# M7103.net
KiCad netlist of a schematic drawn in EAGLE
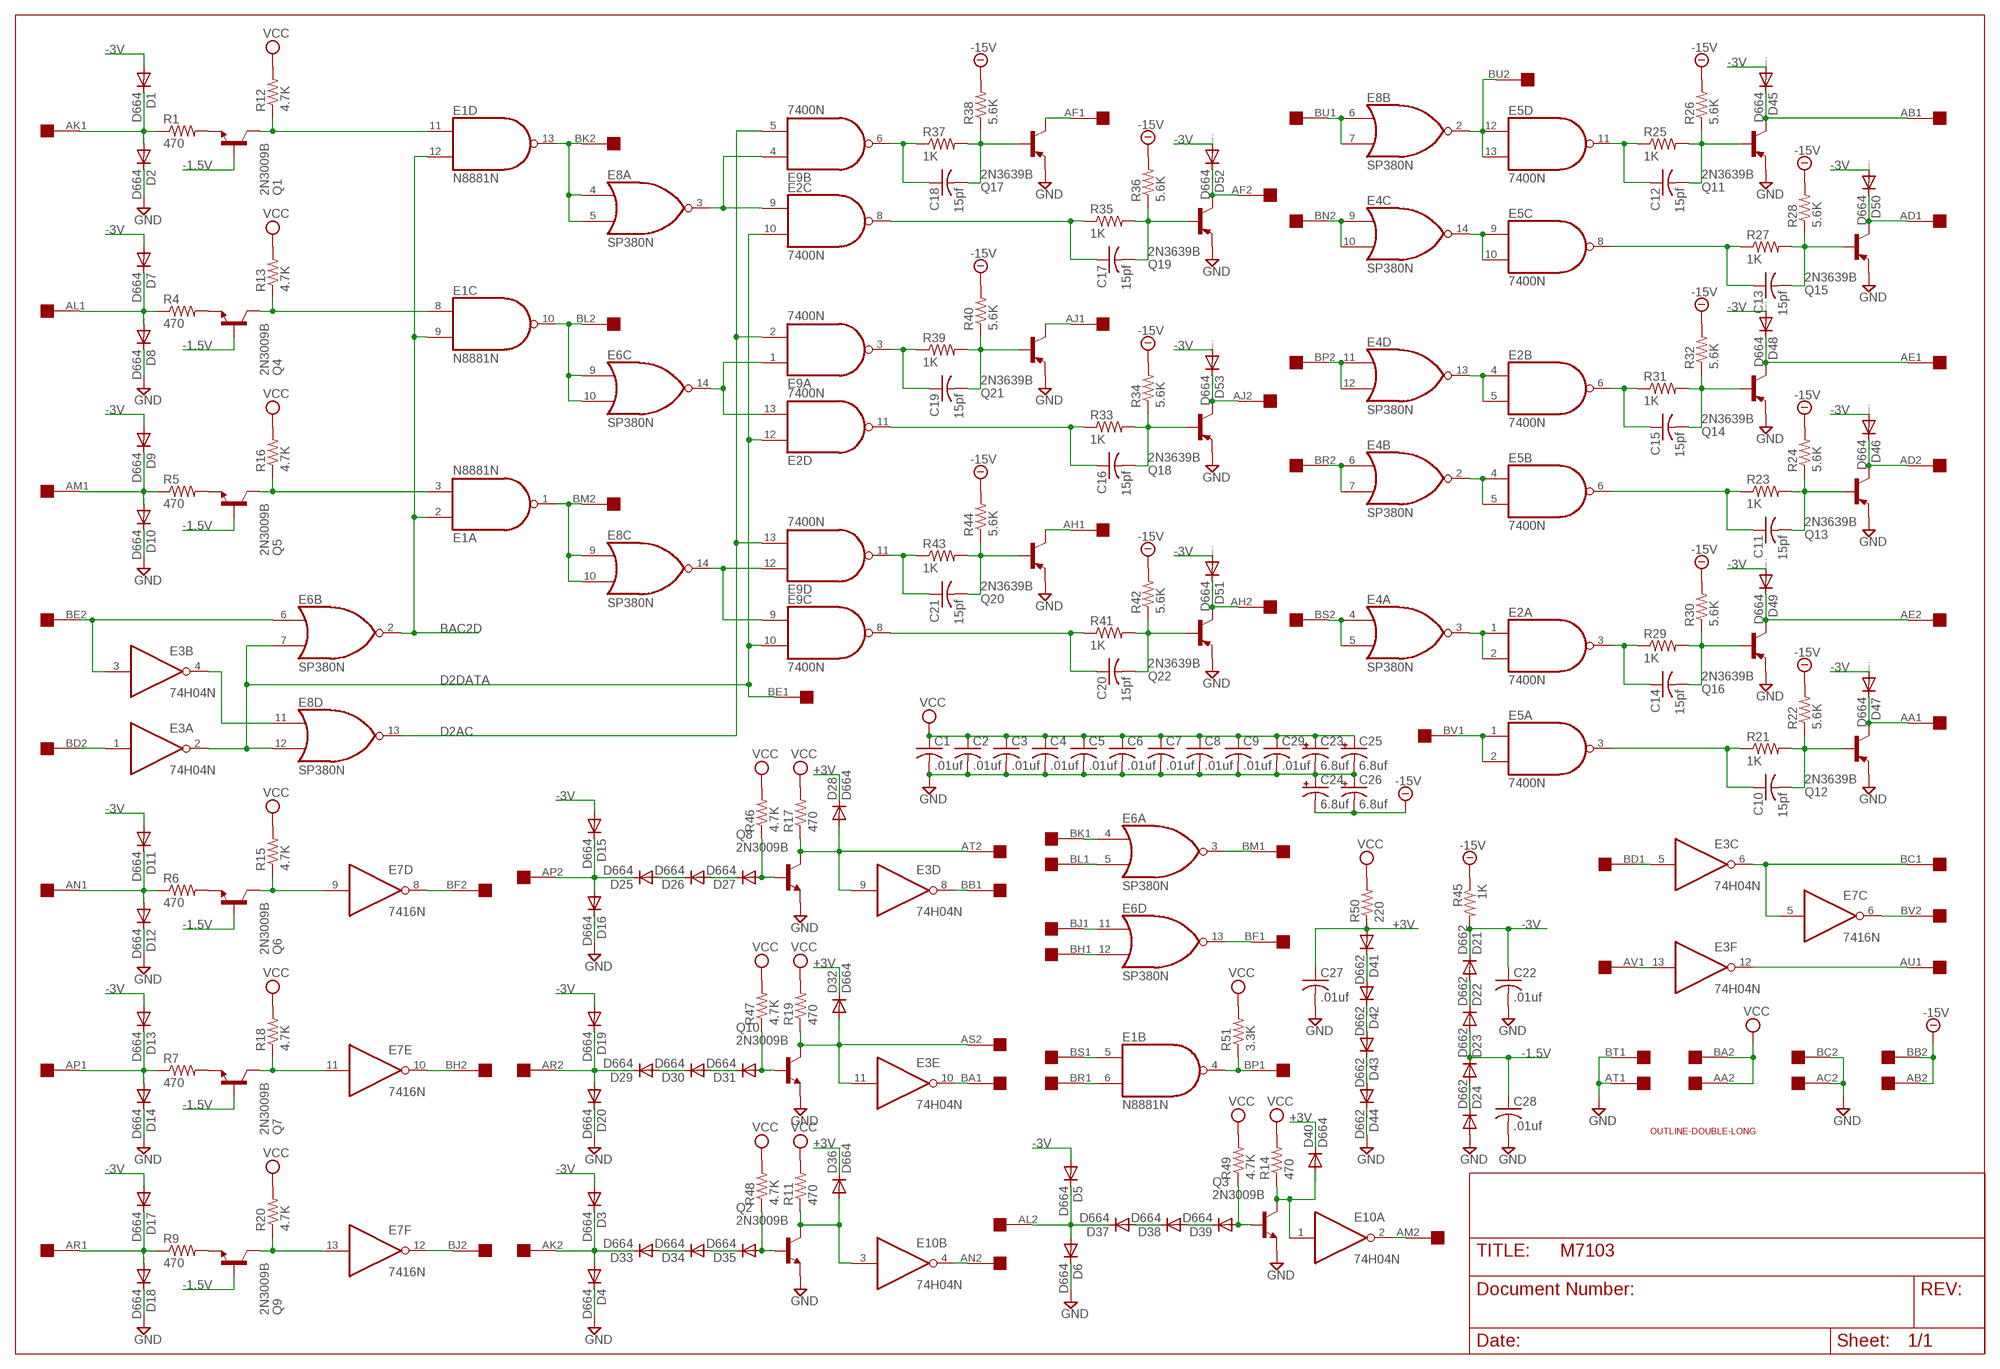
[diagram p0: schematic, sheet 1]

(export (version "E")
  (design (tool "Eeschema 10.0.6"))
  (components
    (comp (ref "C1")
      (value ".01uf")
      (footprint "eagle-import:C050-025X075")
      (libsource (lib "eagle-import") (part "C-US050-025X075"))
    )
    (comp (ref "C2")
      (value ".01uf")
      (footprint "eagle-import:C050-025X075")
      (libsource (lib "eagle-import") (part "C-US050-025X075"))
    )
    (comp (ref "C3")
      (value ".01uf")
      (footprint "eagle-import:C050-025X075")
      (libsource (lib "eagle-import") (part "C-US050-025X075"))
    )
    (comp (ref "C4")
      (value ".01uf")
      (footprint "eagle-import:C050-025X075")
      (libsource (lib "eagle-import") (part "C-US050-025X075"))
    )
    (comp (ref "C5")
      (value ".01uf")
      (footprint "eagle-import:C050-025X075")
      (libsource (lib "eagle-import") (part "C-US050-025X075"))
    )
    (comp (ref "C6")
      (value ".01uf")
      (footprint "eagle-import:C050-025X075")
      (libsource (lib "eagle-import") (part "C-US050-025X075"))
    )
    (comp (ref "C7")
      (value ".01uf")
      (footprint "eagle-import:C050-025X075")
      (libsource (lib "eagle-import") (part "C-US050-025X075"))
    )
    (comp (ref "C8")
      (value ".01uf")
      (footprint "eagle-import:C050-025X075")
      (libsource (lib "eagle-import") (part "C-US050-025X075"))
    )
    (comp (ref "C9")
      (value ".01uf")
      (footprint "eagle-import:C050-025X075")
      (libsource (lib "eagle-import") (part "C-US050-025X075"))
    )
    (comp (ref "C10")
      (value "15pf")
      (footprint "eagle-import:C050-025X075")
      (libsource (lib "eagle-import") (part "C-US050-025X075"))
    )
    (comp (ref "C11")
      (value "15pf")
      (footprint "eagle-import:C050-025X075")
      (libsource (lib "eagle-import") (part "C-US050-025X075"))
    )
    (comp (ref "C12")
      (value "15pf")
      (footprint "eagle-import:C050-025X075")
      (libsource (lib "eagle-import") (part "C-US050-025X075"))
    )
    (comp (ref "C13")
      (value "15pf")
      (footprint "eagle-import:C050-025X075")
      (libsource (lib "eagle-import") (part "C-US050-025X075"))
    )
    (comp (ref "C14")
      (value "15pf")
      (footprint "eagle-import:C050-025X075")
      (libsource (lib "eagle-import") (part "C-US050-025X075"))
    )
    (comp (ref "C15")
      (value "15pf")
      (footprint "eagle-import:C050-025X075")
      (libsource (lib "eagle-import") (part "C-US050-025X075"))
    )
    (comp (ref "C16")
      (value "15pf")
      (footprint "eagle-import:C050-025X075")
      (libsource (lib "eagle-import") (part "C-US050-025X075"))
    )
    (comp (ref "C17")
      (value "15pf")
      (footprint "eagle-import:C050-025X075")
      (libsource (lib "eagle-import") (part "C-US050-025X075"))
    )
    (comp (ref "C18")
      (value "15pf")
      (footprint "eagle-import:C050-025X075")
      (libsource (lib "eagle-import") (part "C-US050-025X075"))
    )
    (comp (ref "C19")
      (value "15pf")
      (footprint "eagle-import:C050-025X075")
      (libsource (lib "eagle-import") (part "C-US050-025X075"))
    )
    (comp (ref "C20")
      (value "15pf")
      (footprint "eagle-import:C050-025X075")
      (libsource (lib "eagle-import") (part "C-US050-025X075"))
    )
    (comp (ref "C21")
      (value "15pf")
      (footprint "eagle-import:C050-025X075")
      (libsource (lib "eagle-import") (part "C-US050-025X075"))
    )
    (comp (ref "C22")
      (value ".01uf")
      (footprint "eagle-import:C050-025X075")
      (libsource (lib "eagle-import") (part "C-US050-025X075"))
    )
    (comp (ref "C23")
      (value "6.8uf")
      (footprint "eagle-import:E15-5")
      (libsource (lib "eagle-import") (part "CPOL-USE15-5AXIAL"))
    )
    (comp (ref "C24")
      (value "6.8uf")
      (footprint "eagle-import:E15-5")
      (libsource (lib "eagle-import") (part "CPOL-USE15-5AXIAL"))
    )
    (comp (ref "C25")
      (value "6.8uf")
      (footprint "eagle-import:E15-5")
      (libsource (lib "eagle-import") (part "CPOL-USE15-5AXIAL"))
    )
    (comp (ref "C26")
      (value "6.8uf")
      (footprint "eagle-import:E15-5")
      (libsource (lib "eagle-import") (part "CPOL-USE15-5AXIAL"))
    )
    (comp (ref "C27")
      (value ".01uf")
      (footprint "eagle-import:C050-025X075")
      (libsource (lib "eagle-import") (part "C-US050-025X075"))
    )
    (comp (ref "C28")
      (value ".01uf")
      (footprint "eagle-import:C050-025X075")
      (libsource (lib "eagle-import") (part "C-US050-025X075"))
    )
    (comp (ref "C29")
      (value ".01uf")
      (footprint "eagle-import:C050-025X075")
      (libsource (lib "eagle-import") (part "C-US050-025X075"))
    )
    (comp (ref "D1")
      (value "D664")
      (footprint "eagle-import:DO35-10")
      (libsource (lib "eagle-import") (part "1N4148DO35-10"))
    )
    (comp (ref "D2")
      (value "D664")
      (footprint "eagle-import:DO35-10")
      (libsource (lib "eagle-import") (part "1N4148DO35-10"))
    )
    (comp (ref "D3")
      (value "D664")
      (footprint "eagle-import:DO35-10")
      (libsource (lib "eagle-import") (part "1N4148DO35-10"))
    )
    (comp (ref "D4")
      (value "D664")
      (footprint "eagle-import:DO35-10")
      (libsource (lib "eagle-import") (part "1N4148DO35-10"))
    )
    (comp (ref "D5")
      (value "D664")
      (footprint "eagle-import:DO35-10")
      (libsource (lib "eagle-import") (part "1N4148DO35-10"))
    )
    (comp (ref "D6")
      (value "D664")
      (footprint "eagle-import:DO35-10")
      (libsource (lib "eagle-import") (part "1N4148DO35-10"))
    )
    (comp (ref "D7")
      (value "D664")
      (footprint "eagle-import:DO35-10")
      (libsource (lib "eagle-import") (part "1N4148DO35-10"))
    )
    (comp (ref "D8")
      (value "D664")
      (footprint "eagle-import:DO35-10")
      (libsource (lib "eagle-import") (part "1N4148DO35-10"))
    )
    (comp (ref "D9")
      (value "D664")
      (footprint "eagle-import:DO35-10")
      (libsource (lib "eagle-import") (part "1N4148DO35-10"))
    )
    (comp (ref "D10")
      (value "D664")
      (footprint "eagle-import:DO35-10")
      (libsource (lib "eagle-import") (part "1N4148DO35-10"))
    )
    (comp (ref "D11")
      (value "D664")
      (footprint "eagle-import:DO35-10")
      (libsource (lib "eagle-import") (part "1N4148DO35-10"))
    )
    (comp (ref "D12")
      (value "D664")
      (footprint "eagle-import:DO35-10")
      (libsource (lib "eagle-import") (part "1N4148DO35-10"))
    )
    (comp (ref "D13")
      (value "D664")
      (footprint "eagle-import:DO35-10")
      (libsource (lib "eagle-import") (part "1N4148DO35-10"))
    )
    (comp (ref "D14")
      (value "D664")
      (footprint "eagle-import:DO35-10")
      (libsource (lib "eagle-import") (part "1N4148DO35-10"))
    )
    (comp (ref "D15")
      (value "D664")
      (footprint "eagle-import:DO35-10")
      (libsource (lib "eagle-import") (part "1N4148DO35-10"))
    )
    (comp (ref "D16")
      (value "D664")
      (footprint "eagle-import:DO35-10")
      (libsource (lib "eagle-import") (part "1N4148DO35-10"))
    )
    (comp (ref "D17")
      (value "D664")
      (footprint "eagle-import:DO35-10")
      (libsource (lib "eagle-import") (part "1N4148DO35-10"))
    )
    (comp (ref "D18")
      (value "D664")
      (footprint "eagle-import:DO35-10")
      (libsource (lib "eagle-import") (part "1N4148DO35-10"))
    )
    (comp (ref "D19")
      (value "D664")
      (footprint "eagle-import:DO35-10")
      (libsource (lib "eagle-import") (part "1N4148DO35-10"))
    )
    (comp (ref "D20")
      (value "D664")
      (footprint "eagle-import:DO35-10")
      (libsource (lib "eagle-import") (part "1N4148DO35-10"))
    )
    (comp (ref "D21")
      (value "D662")
      (footprint "eagle-import:DO35-10")
      (libsource (lib "eagle-import") (part "1N4148DO35-10"))
    )
    (comp (ref "D22")
      (value "D662")
      (footprint "eagle-import:DO35-10")
      (libsource (lib "eagle-import") (part "1N4148DO35-10"))
    )
    (comp (ref "D23")
      (value "D662")
      (footprint "eagle-import:DO35-10")
      (libsource (lib "eagle-import") (part "1N4148DO35-10"))
    )
    (comp (ref "D24")
      (value "D662")
      (footprint "eagle-import:DO35-10")
      (libsource (lib "eagle-import") (part "1N4148DO35-10"))
    )
    (comp (ref "D25")
      (value "D664")
      (footprint "eagle-import:DO35-10")
      (libsource (lib "eagle-import") (part "1N4148DO35-10"))
    )
    (comp (ref "D26")
      (value "D664")
      (footprint "eagle-import:DO35-10")
      (libsource (lib "eagle-import") (part "1N4148DO35-10"))
    )
    (comp (ref "D27")
      (value "D664")
      (footprint "eagle-import:DO35-10")
      (libsource (lib "eagle-import") (part "1N4148DO35-10"))
    )
    (comp (ref "D28")
      (value "D664")
      (footprint "eagle-import:DO35-10")
      (libsource (lib "eagle-import") (part "1N4148DO35-10"))
    )
    (comp (ref "D29")
      (value "D664")
      (footprint "eagle-import:DO35-10")
      (libsource (lib "eagle-import") (part "1N4148DO35-10"))
    )
    (comp (ref "D30")
      (value "D664")
      (footprint "eagle-import:DO35-10")
      (libsource (lib "eagle-import") (part "1N4148DO35-10"))
    )
    (comp (ref "D31")
      (value "D664")
      (footprint "eagle-import:DO35-10")
      (libsource (lib "eagle-import") (part "1N4148DO35-10"))
    )
    (comp (ref "D32")
      (value "D664")
      (footprint "eagle-import:DO35-10")
      (libsource (lib "eagle-import") (part "1N4148DO35-10"))
    )
    (comp (ref "D33")
      (value "D664")
      (footprint "eagle-import:DO35-10")
      (libsource (lib "eagle-import") (part "1N4148DO35-10"))
    )
    (comp (ref "D34")
      (value "D664")
      (footprint "eagle-import:DO35-10")
      (libsource (lib "eagle-import") (part "1N4148DO35-10"))
    )
    (comp (ref "D35")
      (value "D664")
      (footprint "eagle-import:DO35-10")
      (libsource (lib "eagle-import") (part "1N4148DO35-10"))
    )
    (comp (ref "D36")
      (value "D664")
      (footprint "eagle-import:DO35-10")
      (libsource (lib "eagle-import") (part "1N4148DO35-10"))
    )
    (comp (ref "D37")
      (value "D664")
      (footprint "eagle-import:DO35-10")
      (libsource (lib "eagle-import") (part "1N4148DO35-10"))
    )
    (comp (ref "D38")
      (value "D664")
      (footprint "eagle-import:DO35-10")
      (libsource (lib "eagle-import") (part "1N4148DO35-10"))
    )
    (comp (ref "D39")
      (value "D664")
      (footprint "eagle-import:DO35-10")
      (libsource (lib "eagle-import") (part "1N4148DO35-10"))
    )
    (comp (ref "D40")
      (value "D664")
      (footprint "eagle-import:DO35-10")
      (libsource (lib "eagle-import") (part "1N4148DO35-10"))
    )
    (comp (ref "D41")
      (value "D662")
      (footprint "eagle-import:DO35-10")
      (libsource (lib "eagle-import") (part "1N4148DO35-10"))
    )
    (comp (ref "D42")
      (value "D662")
      (footprint "eagle-import:DO35-10")
      (libsource (lib "eagle-import") (part "1N4148DO35-10"))
    )
    (comp (ref "D43")
      (value "D662")
      (footprint "eagle-import:DO35-10")
      (libsource (lib "eagle-import") (part "1N4148DO35-10"))
    )
    (comp (ref "D44")
      (value "D662")
      (footprint "eagle-import:DO35-10")
      (libsource (lib "eagle-import") (part "1N4148DO35-10"))
    )
    (comp (ref "D45")
      (value "D664")
      (footprint "eagle-import:DO35-10")
      (libsource (lib "eagle-import") (part "1N4148DO35-10"))
    )
    (comp (ref "D46")
      (value "D664")
      (footprint "eagle-import:DO35-10")
      (libsource (lib "eagle-import") (part "1N4148DO35-10"))
    )
    (comp (ref "D47")
      (value "D664")
      (footprint "eagle-import:DO35-10")
      (libsource (lib "eagle-import") (part "1N4148DO35-10"))
    )
    (comp (ref "D48")
      (value "D664")
      (footprint "eagle-import:DO35-10")
      (libsource (lib "eagle-import") (part "1N4148DO35-10"))
    )
    (comp (ref "D49")
      (value "D664")
      (footprint "eagle-import:DO35-10")
      (libsource (lib "eagle-import") (part "1N4148DO35-10"))
    )
    (comp (ref "D50")
      (value "D664")
      (footprint "eagle-import:DO35-10")
      (libsource (lib "eagle-import") (part "1N4148DO35-10"))
    )
    (comp (ref "D51")
      (value "D664")
      (footprint "eagle-import:DO35-10")
      (libsource (lib "eagle-import") (part "1N4148DO35-10"))
    )
    (comp (ref "D52")
      (value "D664")
      (footprint "eagle-import:DO35-10")
      (libsource (lib "eagle-import") (part "1N4148DO35-10"))
    )
    (comp (ref "D53")
      (value "D664")
      (footprint "eagle-import:DO35-10")
      (libsource (lib "eagle-import") (part "1N4148DO35-10"))
    )
    (comp (ref "E1")
      (value "N8881N")
      (footprint "eagle-import:DIL14")
      (libsource (lib "eagle-import") (part "N8881N"))
    )
    (comp (ref "E2")
      (value "7400N")
      (footprint "eagle-import:DIL14")
      (libsource (lib "eagle-import") (part "7400N"))
    )
    (comp (ref "E3")
      (value "74H04N")
      (footprint "eagle-import:DIL14")
      (libsource (lib "eagle-import") (part "7404N"))
    )
    (comp (ref "E4")
      (value "SP380N")
      (footprint "eagle-import:DIL14")
      (libsource (lib "eagle-import") (part "SP380N"))
    )
    (comp (ref "E5")
      (value "7400N")
      (footprint "eagle-import:DIL14")
      (libsource (lib "eagle-import") (part "7400N"))
    )
    (comp (ref "E6")
      (value "SP380N")
      (footprint "eagle-import:DIL14")
      (libsource (lib "eagle-import") (part "SP380N"))
    )
    (comp (ref "E7")
      (value "7416N")
      (footprint "eagle-import:DIL14")
      (libsource (lib "eagle-import") (part "7416N"))
    )
    (comp (ref "E8")
      (value "SP380N")
      (footprint "eagle-import:DIL14")
      (libsource (lib "eagle-import") (part "SP380N"))
    )
    (comp (ref "E9")
      (value "7400N")
      (footprint "eagle-import:DIL14")
      (libsource (lib "eagle-import") (part "7400N"))
    )
    (comp (ref "E10")
      (value "74H04N")
      (footprint "eagle-import:DIL14")
      (libsource (lib "eagle-import") (part "7404N"))
    )
    (comp (ref "EDGE")
      (value "DOUBLE")
      (footprint "eagle-import:EDGE-CON4")
      (libsource (lib "eagle-import") (part "DOUBLE"))
    )
    (comp (ref "Q1")
      (value "2N3009B")
      (footprint "eagle-import:TO39")
      (libsource (lib "eagle-import") (part "2N3019"))
    )
    (comp (ref "Q2")
      (value "2N3009B")
      (footprint "eagle-import:TO39")
      (libsource (lib "eagle-import") (part "2N3019"))
    )
    (comp (ref "Q3")
      (value "2N3009B")
      (footprint "eagle-import:TO39")
      (libsource (lib "eagle-import") (part "2N3019"))
    )
    (comp (ref "Q4")
      (value "2N3009B")
      (footprint "eagle-import:TO39")
      (libsource (lib "eagle-import") (part "2N3019"))
    )
    (comp (ref "Q5")
      (value "2N3009B")
      (footprint "eagle-import:TO39")
      (libsource (lib "eagle-import") (part "2N3019"))
    )
    (comp (ref "Q6")
      (value "2N3009B")
      (footprint "eagle-import:TO39")
      (libsource (lib "eagle-import") (part "2N3019"))
    )
    (comp (ref "Q7")
      (value "2N3009B")
      (footprint "eagle-import:TO39")
      (libsource (lib "eagle-import") (part "2N3019"))
    )
    (comp (ref "Q8")
      (value "2N3009B")
      (footprint "eagle-import:TO39")
      (libsource (lib "eagle-import") (part "2N3019"))
    )
    (comp (ref "Q9")
      (value "2N3009B")
      (footprint "eagle-import:TO39")
      (libsource (lib "eagle-import") (part "2N3019"))
    )
    (comp (ref "Q10")
      (value "2N3009B")
      (footprint "eagle-import:TO39")
      (libsource (lib "eagle-import") (part "2N3019"))
    )
    (comp (ref "Q11")
      (value "2N3639B")
      (footprint "eagle-import:TO39")
      (libsource (lib "eagle-import") (part "2N3637"))
    )
    (comp (ref "Q12")
      (value "2N3639B")
      (footprint "eagle-import:TO39")
      (libsource (lib "eagle-import") (part "2N3637"))
    )
    (comp (ref "Q13")
      (value "2N3639B")
      (footprint "eagle-import:TO39")
      (libsource (lib "eagle-import") (part "2N3637"))
    )
    (comp (ref "Q14")
      (value "2N3639B")
      (footprint "eagle-import:TO39")
      (libsource (lib "eagle-import") (part "2N3637"))
    )
    (comp (ref "Q15")
      (value "2N3639B")
      (footprint "eagle-import:TO39")
      (libsource (lib "eagle-import") (part "2N3637"))
    )
    (comp (ref "Q16")
      (value "2N3639B")
      (footprint "eagle-import:TO39")
      (libsource (lib "eagle-import") (part "2N3637"))
    )
    (comp (ref "Q17")
      (value "2N3639B")
      (footprint "eagle-import:TO39")
      (libsource (lib "eagle-import") (part "2N3637"))
    )
    (comp (ref "Q18")
      (value "2N3639B")
      (footprint "eagle-import:TO39")
      (libsource (lib "eagle-import") (part "2N3637"))
    )
    (comp (ref "Q19")
      (value "2N3639B")
      (footprint "eagle-import:TO39")
      (libsource (lib "eagle-import") (part "2N3637"))
    )
    (comp (ref "Q20")
      (value "2N3639B")
      (footprint "eagle-import:TO39")
      (libsource (lib "eagle-import") (part "2N3637"))
    )
    (comp (ref "Q21")
      (value "2N3639B")
      (footprint "eagle-import:TO39")
      (libsource (lib "eagle-import") (part "2N3637"))
    )
    (comp (ref "Q22")
      (value "2N3639B")
      (footprint "eagle-import:TO39")
      (libsource (lib "eagle-import") (part "2N3637"))
    )
    (comp (ref "R1")
      (value "470")
      (footprint "eagle-import:0207_10")
      (libsource (lib "eagle-import") (part "R-US_0207/10"))
    )
    (comp (ref "R4")
      (value "470")
      (footprint "eagle-import:0207_10")
      (libsource (lib "eagle-import") (part "R-US_0207/10"))
    )
    (comp (ref "R5")
      (value "470")
      (footprint "eagle-import:0207_10")
      (libsource (lib "eagle-import") (part "R-US_0207/10"))
    )
    (comp (ref "R6")
      (value "470")
      (footprint "eagle-import:0207_10")
      (libsource (lib "eagle-import") (part "R-US_0207/10"))
    )
    (comp (ref "R7")
      (value "470")
      (footprint "eagle-import:0207_10")
      (libsource (lib "eagle-import") (part "R-US_0207/10"))
    )
    (comp (ref "R9")
      (value "470")
      (footprint "eagle-import:0207_10")
      (libsource (lib "eagle-import") (part "R-US_0207/10"))
    )
    (comp (ref "R11")
      (value "470")
      (footprint "eagle-import:0207_10")
      (libsource (lib "eagle-import") (part "R-US_0207/10"))
    )
    (comp (ref "R12")
      (value "4.7K")
      (footprint "eagle-import:0207_10")
      (libsource (lib "eagle-import") (part "R-US_0207/10"))
    )
    (comp (ref "R13")
      (value "4.7K")
      (footprint "eagle-import:0207_10")
      (libsource (lib "eagle-import") (part "R-US_0207/10"))
    )
    (comp (ref "R14")
      (value "470")
      (footprint "eagle-import:0207_10")
      (libsource (lib "eagle-import") (part "R-US_0207/10"))
    )
    (comp (ref "R15")
      (value "4.7K")
      (footprint "eagle-import:0207_10")
      (libsource (lib "eagle-import") (part "R-US_0207/10"))
    )
    (comp (ref "R16")
      (value "4.7K")
      (footprint "eagle-import:0207_10")
      (libsource (lib "eagle-import") (part "R-US_0207/10"))
    )
    (comp (ref "R17")
      (value "470")
      (footprint "eagle-import:0207_10")
      (libsource (lib "eagle-import") (part "R-US_0207/10"))
    )
    (comp (ref "R18")
      (value "4.7K")
      (footprint "eagle-import:0207_10")
      (libsource (lib "eagle-import") (part "R-US_0207/10"))
    )
    (comp (ref "R19")
      (value "470")
      (footprint "eagle-import:0207_10")
      (libsource (lib "eagle-import") (part "R-US_0207/10"))
    )
    (comp (ref "R20")
      (value "4.7K")
      (footprint "eagle-import:0207_10")
      (libsource (lib "eagle-import") (part "R-US_0207/10"))
    )
    (comp (ref "R21")
      (value "1K")
      (footprint "eagle-import:0207_10")
      (libsource (lib "eagle-import") (part "R-US_0207/10"))
    )
    (comp (ref "R22")
      (value "5.6K")
      (footprint "eagle-import:0207_10")
      (libsource (lib "eagle-import") (part "R-US_0207/10"))
    )
    (comp (ref "R23")
      (value "1K")
      (footprint "eagle-import:0207_10")
      (libsource (lib "eagle-import") (part "R-US_0207/10"))
    )
    (comp (ref "R24")
      (value "5.6K")
      (footprint "eagle-import:0207_10")
      (libsource (lib "eagle-import") (part "R-US_0207/10"))
    )
    (comp (ref "R25")
      (value "1K")
      (footprint "eagle-import:0207_10")
      (libsource (lib "eagle-import") (part "R-US_0207/10"))
    )
    (comp (ref "R26")
      (value "5.6K")
      (footprint "eagle-import:0207_10")
      (libsource (lib "eagle-import") (part "R-US_0207/10"))
    )
    (comp (ref "R27")
      (value "1K")
      (footprint "eagle-import:0207_10")
      (libsource (lib "eagle-import") (part "R-US_0207/10"))
    )
    (comp (ref "R28")
      (value "5.6K")
      (footprint "eagle-import:0207_10")
      (libsource (lib "eagle-import") (part "R-US_0207/10"))
    )
    (comp (ref "R29")
      (value "1K")
      (footprint "eagle-import:0207_10")
      (libsource (lib "eagle-import") (part "R-US_0207/10"))
    )
    (comp (ref "R30")
      (value "5.6K")
      (footprint "eagle-import:0207_10")
      (libsource (lib "eagle-import") (part "R-US_0207/10"))
    )
    (comp (ref "R31")
      (value "1K")
      (footprint "eagle-import:0207_10")
      (libsource (lib "eagle-import") (part "R-US_0207/10"))
    )
    (comp (ref "R32")
      (value "5.6K")
      (footprint "eagle-import:0207_10")
      (libsource (lib "eagle-import") (part "R-US_0207/10"))
    )
    (comp (ref "R33")
      (value "1K")
      (footprint "eagle-import:0207_10")
      (libsource (lib "eagle-import") (part "R-US_0207/10"))
    )
    (comp (ref "R34")
      (value "5.6K")
      (footprint "eagle-import:0207_10")
      (libsource (lib "eagle-import") (part "R-US_0207/10"))
    )
    (comp (ref "R35")
      (value "1K")
      (footprint "eagle-import:0207_10")
      (libsource (lib "eagle-import") (part "R-US_0207/10"))
    )
    (comp (ref "R36")
      (value "5.6K")
      (footprint "eagle-import:0207_10")
      (libsource (lib "eagle-import") (part "R-US_0207/10"))
    )
    (comp (ref "R37")
      (value "1K")
      (footprint "eagle-import:0207_10")
      (libsource (lib "eagle-import") (part "R-US_0207/10"))
    )
    (comp (ref "R38")
      (value "5.6K")
      (footprint "eagle-import:0207_10")
      (libsource (lib "eagle-import") (part "R-US_0207/10"))
    )
    (comp (ref "R39")
      (value "1K")
      (footprint "eagle-import:0207_10")
      (libsource (lib "eagle-import") (part "R-US_0207/10"))
    )
    (comp (ref "R40")
      (value "5.6K")
      (footprint "eagle-import:0207_10")
      (libsource (lib "eagle-import") (part "R-US_0207/10"))
    )
    (comp (ref "R41")
      (value "1K")
      (footprint "eagle-import:0207_10")
      (libsource (lib "eagle-import") (part "R-US_0207/10"))
    )
    (comp (ref "R42")
      (value "5.6K")
      (footprint "eagle-import:0207_10")
      (libsource (lib "eagle-import") (part "R-US_0207/10"))
    )
    (comp (ref "R43")
      (value "1K")
      (footprint "eagle-import:0207_10")
      (libsource (lib "eagle-import") (part "R-US_0207/10"))
    )
    (comp (ref "R44")
      (value "5.6K")
      (footprint "eagle-import:0207_10")
      (libsource (lib "eagle-import") (part "R-US_0207/10"))
    )
    (comp (ref "R45")
      (value "1K")
      (footprint "eagle-import:0207_10")
      (libsource (lib "eagle-import") (part "R-US_0207/10"))
    )
    (comp (ref "R46")
      (value "4.7K")
      (footprint "eagle-import:0207_10")
      (libsource (lib "eagle-import") (part "R-US_0207/10"))
    )
    (comp (ref "R47")
      (value "4.7K")
      (footprint "eagle-import:0207_10")
      (libsource (lib "eagle-import") (part "R-US_0207/10"))
    )
    (comp (ref "R48")
      (value "4.7K")
      (footprint "eagle-import:0207_10")
      (libsource (lib "eagle-import") (part "R-US_0207/10"))
    )
    (comp (ref "R49")
      (value "4.7K")
      (footprint "eagle-import:0207_10")
      (libsource (lib "eagle-import") (part "R-US_0207/10"))
    )
    (comp (ref "R50")
      (value "220")
      (footprint "eagle-import:0207_10")
      (libsource (lib "eagle-import") (part "R-US_0207/10"))
    )
    (comp (ref "R51")
      (value "3.3K")
      (footprint "eagle-import:0207_10")
      (libsource (lib "eagle-import") (part "R-US_0207/10"))
    )
    (comp (ref "U$3")
      (value "OUTLINE-DOUBLE-LONG")
      (footprint "eagle-import:DOUBLE-LONG")
      (libsource (lib "eagle-import") (part "OUTLINE-DOUBLE-LONG"))
    )
  )
  (nets
    (net (code "1") (name "-15V") (class "Default")
      (node (ref "C24") (pin "-") (pinfunction "-_-") (pintype "passive"))
      (node (ref "C26") (pin "-") (pinfunction "-_-") (pintype "passive"))
      (node (ref "EDGE") (pin "AB2") (pinfunction "1_AB2") (pintype "bidirectional"))
      (node (ref "EDGE") (pin "BB2") (pinfunction "1_BB2") (pintype "bidirectional"))
      (node (ref "R22") (pin "2") (pinfunction "2_2") (pintype "passive"))
      (node (ref "R24") (pin "2") (pinfunction "2_2") (pintype "passive"))
      (node (ref "R26") (pin "2") (pinfunction "2_2") (pintype "passive"))
      (node (ref "R28") (pin "2") (pinfunction "2_2") (pintype "passive"))
      (node (ref "R30") (pin "2") (pinfunction "2_2") (pintype "passive"))
      (node (ref "R32") (pin "2") (pinfunction "2_2") (pintype "passive"))
      (node (ref "R34") (pin "2") (pinfunction "2_2") (pintype "passive"))
      (node (ref "R36") (pin "2") (pinfunction "2_2") (pintype "passive"))
      (node (ref "R38") (pin "2") (pinfunction "2_2") (pintype "passive"))
      (node (ref "R40") (pin "2") (pinfunction "2_2") (pintype "passive"))
      (node (ref "R42") (pin "2") (pinfunction "2_2") (pintype "passive"))
      (node (ref "R44") (pin "2") (pinfunction "2_2") (pintype "passive"))
      (node (ref "R45") (pin "1") (pinfunction "1_1") (pintype "passive"))
    )
    (net (code "2") (name "/+3V") (class "Default")
      (node (ref "C27") (pin "1") (pinfunction "1_1") (pintype "passive"))
      (node (ref "D28") (pin "C") (pinfunction "C_C") (pintype "passive"))
      (node (ref "D32") (pin "C") (pinfunction "C_C") (pintype "passive"))
      (node (ref "D36") (pin "C") (pinfunction "C_C") (pintype "passive"))
      (node (ref "D40") (pin "C") (pinfunction "C_C") (pintype "passive"))
      (node (ref "D41") (pin "A") (pinfunction "A_A") (pintype "passive"))
      (node (ref "R50") (pin "1") (pinfunction "1_1") (pintype "passive"))
    )
    (net (code "3") (name "/-1.5V") (class "Default")
      (node (ref "C28") (pin "1") (pinfunction "1_1") (pintype "passive"))
      (node (ref "D22") (pin "A") (pinfunction "A_A") (pintype "passive"))
      (node (ref "D23") (pin "C") (pinfunction "C_C") (pintype "passive"))
      (node (ref "Q1") (pin "2") (pinfunction "B_2") (pintype "passive"))
      (node (ref "Q4") (pin "2") (pinfunction "B_2") (pintype "passive"))
      (node (ref "Q5") (pin "2") (pinfunction "B_2") (pintype "passive"))
      (node (ref "Q6") (pin "2") (pinfunction "B_2") (pintype "passive"))
      (node (ref "Q7") (pin "2") (pinfunction "B_2") (pintype "passive"))
      (node (ref "Q9") (pin "2") (pinfunction "B_2") (pintype "passive"))
    )
    (net (code "4") (name "/-3V") (class "Default")
      (node (ref "C22") (pin "1") (pinfunction "1_1") (pintype "passive"))
      (node (ref "D1") (pin "A") (pinfunction "A_A") (pintype "passive"))
      (node (ref "D11") (pin "A") (pinfunction "A_A") (pintype "passive"))
      (node (ref "D13") (pin "A") (pinfunction "A_A") (pintype "passive"))
      (node (ref "D15") (pin "A") (pinfunction "A_A") (pintype "passive"))
      (node (ref "D17") (pin "A") (pinfunction "A_A") (pintype "passive"))
      (node (ref "D19") (pin "A") (pinfunction "A_A") (pintype "passive"))
      (node (ref "D21") (pin "C") (pinfunction "C_C") (pintype "passive"))
      (node (ref "D3") (pin "A") (pinfunction "A_A") (pintype "passive"))
      (node (ref "D45") (pin "A") (pinfunction "A_A") (pintype "passive"))
      (node (ref "D46") (pin "A") (pinfunction "A_A") (pintype "passive"))
      (node (ref "D47") (pin "A") (pinfunction "A_A") (pintype "passive"))
      (node (ref "D48") (pin "A") (pinfunction "A_A") (pintype "passive"))
      (node (ref "D49") (pin "A") (pinfunction "A_A") (pintype "passive"))
      (node (ref "D5") (pin "A") (pinfunction "A_A") (pintype "passive"))
      (node (ref "D50") (pin "A") (pinfunction "A_A") (pintype "passive"))
      (node (ref "D51") (pin "A") (pinfunction "A_A") (pintype "passive"))
      (node (ref "D52") (pin "A") (pinfunction "A_A") (pintype "passive"))
      (node (ref "D53") (pin "A") (pinfunction "A_A") (pintype "passive"))
      (node (ref "D7") (pin "A") (pinfunction "A_A") (pintype "passive"))
      (node (ref "D9") (pin "A") (pinfunction "A_A") (pintype "passive"))
      (node (ref "R45") (pin "2") (pinfunction "2_2") (pintype "passive"))
    )
    (net (code "5") (name "/BAC2D") (class "Default")
      (node (ref "E1") (pin "12") (pinfunction "I1_12") (pintype "input"))
      (node (ref "E1") (pin "2") (pinfunction "I0_2") (pintype "input"))
      (node (ref "E1") (pin "9") (pinfunction "I1_9") (pintype "input"))
      (node (ref "E6") (pin "2") (pinfunction "O_2") (pintype "output"))
    )
    (net (code "6") (name "/D2AC") (class "Default")
      (node (ref "E8") (pin "13") (pinfunction "O_13") (pintype "output"))
      (node (ref "E9") (pin "13") (pinfunction "I1_13") (pintype "input"))
      (node (ref "E9") (pin "2") (pinfunction "I1_2") (pintype "input"))
      (node (ref "E9") (pin "5") (pinfunction "I1_5") (pintype "input"))
    )
    (net (code "7") (name "/D2DATA") (class "Default")
      (node (ref "E2") (pin "10") (pinfunction "I1_10") (pintype "input"))
      (node (ref "E2") (pin "12") (pinfunction "I0_12") (pintype "input"))
      (node (ref "E3") (pin "2") (pinfunction "O_2") (pintype "output"))
      (node (ref "E6") (pin "7") (pinfunction "I1_7") (pintype "input"))
      (node (ref "E8") (pin "12") (pinfunction "I1_12") (pintype "input"))
      (node (ref "E9") (pin "10") (pinfunction "I1_10") (pintype "input"))
      (node (ref "EDGE") (pin "BE1") (pinfunction "1_BE1") (pintype "bidirectional"))
    )
    (net (code "8") (name "GND") (class "Default")
      (node (ref "C1") (pin "2") (pinfunction "2_2") (pintype "passive"))
      (node (ref "C2") (pin "2") (pinfunction "2_2") (pintype "passive"))
      (node (ref "C22") (pin "2") (pinfunction "2_2") (pintype "passive"))
      (node (ref "C23") (pin "-") (pinfunction "-_-") (pintype "passive"))
      (node (ref "C24") (pin "+") (pinfunction "+_+") (pintype "passive"))
      (node (ref "C25") (pin "-") (pinfunction "-_-") (pintype "passive"))
      (node (ref "C26") (pin "+") (pinfunction "+_+") (pintype "passive"))
      (node (ref "C27") (pin "2") (pinfunction "2_2") (pintype "passive"))
      (node (ref "C28") (pin "2") (pinfunction "2_2") (pintype "passive"))
      (node (ref "C29") (pin "2") (pinfunction "2_2") (pintype "passive"))
      (node (ref "C3") (pin "2") (pinfunction "2_2") (pintype "passive"))
      (node (ref "C4") (pin "2") (pinfunction "2_2") (pintype "passive"))
      (node (ref "C5") (pin "2") (pinfunction "2_2") (pintype "passive"))
      (node (ref "C6") (pin "2") (pinfunction "2_2") (pintype "passive"))
      (node (ref "C7") (pin "2") (pinfunction "2_2") (pintype "passive"))
      (node (ref "C8") (pin "2") (pinfunction "2_2") (pintype "passive"))
      (node (ref "C9") (pin "2") (pinfunction "2_2") (pintype "passive"))
      (node (ref "D10") (pin "C") (pinfunction "C_C") (pintype "passive"))
      (node (ref "D12") (pin "C") (pinfunction "C_C") (pintype "passive"))
      (node (ref "D14") (pin "C") (pinfunction "C_C") (pintype "passive"))
      (node (ref "D16") (pin "C") (pinfunction "C_C") (pintype "passive"))
      (node (ref "D18") (pin "C") (pinfunction "C_C") (pintype "passive"))
      (node (ref "D2") (pin "C") (pinfunction "C_C") (pintype "passive"))
      (node (ref "D20") (pin "C") (pinfunction "C_C") (pintype "passive"))
      (node (ref "D24") (pin "A") (pinfunction "A_A") (pintype "passive"))
      (node (ref "D4") (pin "C") (pinfunction "C_C") (pintype "passive"))
      (node (ref "D44") (pin "C") (pinfunction "C_C") (pintype "passive"))
      (node (ref "D6") (pin "C") (pinfunction "C_C") (pintype "passive"))
      (node (ref "D8") (pin "C") (pinfunction "C_C") (pintype "passive"))
      (node (ref "EDGE") (pin "AC2") (pinfunction "1_AC2") (pintype "bidirectional"))
      (node (ref "EDGE") (pin "AT1") (pinfunction "1_AT1") (pintype "bidirectional"))
      (node (ref "EDGE") (pin "BC2") (pinfunction "1_BC2") (pintype "bidirectional"))
      (node (ref "EDGE") (pin "BT1") (pinfunction "1_BT1") (pintype "bidirectional"))
      (node (ref "Q10") (pin "1") (pinfunction "E_1") (pintype "passive"))
      (node (ref "Q11") (pin "1") (pinfunction "E_1") (pintype "passive"))
      (node (ref "Q12") (pin "1") (pinfunction "E_1") (pintype "passive"))
      (node (ref "Q13") (pin "1") (pinfunction "E_1") (pintype "passive"))
      (node (ref "Q14") (pin "1") (pinfunction "E_1") (pintype "passive"))
      (node (ref "Q15") (pin "1") (pinfunction "E_1") (pintype "passive"))
      (node (ref "Q16") (pin "1") (pinfunction "E_1") (pintype "passive"))
      (node (ref "Q17") (pin "1") (pinfunction "E_1") (pintype "passive"))
      (node (ref "Q18") (pin "1") (pinfunction "E_1") (pintype "passive"))
      (node (ref "Q19") (pin "1") (pinfunction "E_1") (pintype "passive"))
      (node (ref "Q2") (pin "1") (pinfunction "E_1") (pintype "passive"))
      (node (ref "Q20") (pin "1") (pinfunction "E_1") (pintype "passive"))
      (node (ref "Q21") (pin "1") (pinfunction "E_1") (pintype "passive"))
      (node (ref "Q22") (pin "1") (pinfunction "E_1") (pintype "passive"))
      (node (ref "Q3") (pin "1") (pinfunction "E_1") (pintype "passive"))
      (node (ref "Q8") (pin "1") (pinfunction "E_1") (pintype "passive"))
    )
    (net (code "9") (name "Net-(D21-PadA)") (class "Default")
      (node (ref "D21") (pin "A") (pinfunction "A_A") (pintype "passive"))
      (node (ref "D22") (pin "C") (pinfunction "C_C") (pintype "passive"))
    )
    (net (code "10") (name "Net-(D23-PadA)") (class "Default")
      (node (ref "D23") (pin "A") (pinfunction "A_A") (pintype "passive"))
      (node (ref "D24") (pin "C") (pinfunction "C_C") (pintype "passive"))
    )
    (net (code "11") (name "Net-(D25-PadA)") (class "Default")
      (node (ref "D25") (pin "A") (pinfunction "A_A") (pintype "passive"))
      (node (ref "D26") (pin "C") (pinfunction "C_C") (pintype "passive"))
    )
    (net (code "12") (name "Net-(D26-PadA)") (class "Default")
      (node (ref "D26") (pin "A") (pinfunction "A_A") (pintype "passive"))
      (node (ref "D27") (pin "C") (pinfunction "C_C") (pintype "passive"))
    )
    (net (code "13") (name "Net-(D29-PadA)") (class "Default")
      (node (ref "D29") (pin "A") (pinfunction "A_A") (pintype "passive"))
      (node (ref "D30") (pin "C") (pinfunction "C_C") (pintype "passive"))
    )
    (net (code "14") (name "Net-(D30-PadA)") (class "Default")
      (node (ref "D30") (pin "A") (pinfunction "A_A") (pintype "passive"))
      (node (ref "D31") (pin "C") (pinfunction "C_C") (pintype "passive"))
    )
    (net (code "15") (name "Net-(D33-PadA)") (class "Default")
      (node (ref "D33") (pin "A") (pinfunction "A_A") (pintype "passive"))
      (node (ref "D34") (pin "C") (pinfunction "C_C") (pintype "passive"))
    )
    (net (code "16") (name "Net-(D34-PadA)") (class "Default")
      (node (ref "D34") (pin "A") (pinfunction "A_A") (pintype "passive"))
      (node (ref "D35") (pin "C") (pinfunction "C_C") (pintype "passive"))
    )
    (net (code "17") (name "Net-(D37-PadA)") (class "Default")
      (node (ref "D37") (pin "A") (pinfunction "A_A") (pintype "passive"))
      (node (ref "D38") (pin "C") (pinfunction "C_C") (pintype "passive"))
    )
    (net (code "18") (name "Net-(D38-PadA)") (class "Default")
      (node (ref "D38") (pin "A") (pinfunction "A_A") (pintype "passive"))
      (node (ref "D39") (pin "C") (pinfunction "C_C") (pintype "passive"))
    )
    (net (code "19") (name "Net-(D41-PadC)") (class "Default")
      (node (ref "D41") (pin "C") (pinfunction "C_C") (pintype "passive"))
      (node (ref "D42") (pin "A") (pinfunction "A_A") (pintype "passive"))
    )
    (net (code "20") (name "Net-(D42-PadC)") (class "Default")
      (node (ref "D42") (pin "C") (pinfunction "C_C") (pintype "passive"))
      (node (ref "D43") (pin "A") (pinfunction "A_A") (pintype "passive"))
    )
    (net (code "21") (name "Net-(D43-PadC)") (class "Default")
      (node (ref "D43") (pin "C") (pinfunction "C_C") (pintype "passive"))
      (node (ref "D44") (pin "A") (pinfunction "A_A") (pintype "passive"))
    )
    (net (code "22") (name "Net-(E1A-I1)") (class "Default")
      (node (ref "E1") (pin "3") (pinfunction "I1_3") (pintype "input"))
      (node (ref "Q5") (pin "3") (pinfunction "C_3") (pintype "passive"))
      (node (ref "R16") (pin "1") (pinfunction "1_1") (pintype "passive"))
    )
    (net (code "23") (name "Net-(E1A-O)") (class "Default")
      (node (ref "E1") (pin "1") (pinfunction "O_1") (pintype "open_collector"))
      (node (ref "E8") (pin "10") (pinfunction "I1_10") (pintype "input"))
      (node (ref "E8") (pin "9") (pinfunction "I0_9") (pintype "input"))
      (node (ref "EDGE") (pin "BM2") (pinfunction "1_BM2") (pintype "bidirectional"))
    )
    (net (code "24") (name "Net-(E1B-I0)") (class "Default")
      (node (ref "E1") (pin "5") (pinfunction "I0_5") (pintype "input"))
      (node (ref "EDGE") (pin "BS1") (pinfunction "1_BS1") (pintype "bidirectional"))
    )
    (net (code "25") (name "Net-(E1B-I1)") (class "Default")
      (node (ref "E1") (pin "6") (pinfunction "I1_6") (pintype "input"))
      (node (ref "EDGE") (pin "BR1") (pinfunction "1_BR1") (pintype "bidirectional"))
    )
    (net (code "26") (name "Net-(E1B-O)") (class "Default")
      (node (ref "E1") (pin "4") (pinfunction "O_4") (pintype "open_collector"))
      (node (ref "EDGE") (pin "BP1") (pinfunction "1_BP1") (pintype "bidirectional"))
      (node (ref "R51") (pin "1") (pinfunction "1_1") (pintype "passive"))
    )
    (net (code "27") (name "Net-(E1C-I0)") (class "Default")
      (node (ref "E1") (pin "8") (pinfunction "I0_8") (pintype "input"))
      (node (ref "Q4") (pin "3") (pinfunction "C_3") (pintype "passive"))
      (node (ref "R13") (pin "1") (pinfunction "1_1") (pintype "passive"))
    )
    (net (code "28") (name "Net-(E1C-O)") (class "Default")
      (node (ref "E1") (pin "10") (pinfunction "O_10") (pintype "open_collector"))
      (node (ref "E6") (pin "10") (pinfunction "I1_10") (pintype "input"))
      (node (ref "E6") (pin "9") (pinfunction "I0_9") (pintype "input"))
      (node (ref "EDGE") (pin "BL2") (pinfunction "1_BL2") (pintype "bidirectional"))
    )
    (net (code "29") (name "Net-(E1D-I0)") (class "Default")
      (node (ref "E1") (pin "11") (pinfunction "I0_11") (pintype "input"))
      (node (ref "Q1") (pin "3") (pinfunction "C_3") (pintype "passive"))
      (node (ref "R12") (pin "1") (pinfunction "1_1") (pintype "passive"))
    )
    (net (code "30") (name "Net-(E1D-O)") (class "Default")
      (node (ref "E1") (pin "13") (pinfunction "O_13") (pintype "open_collector"))
      (node (ref "E8") (pin "4") (pinfunction "I0_4") (pintype "input"))
      (node (ref "E8") (pin "5") (pinfunction "I1_5") (pintype "input"))
      (node (ref "EDGE") (pin "BK2") (pinfunction "1_BK2") (pintype "bidirectional"))
    )
    (net (code "31") (name "Net-(E2A-I0)") (class "Default")
      (node (ref "E2") (pin "1") (pinfunction "I0_1") (pintype "input"))
      (node (ref "E2") (pin "2") (pinfunction "I1_2") (pintype "input"))
      (node (ref "E4") (pin "3") (pinfunction "O_3") (pintype "output"))
    )
    (net (code "32") (name "Net-(E2A-O)") (class "Default")
      (node (ref "C14") (pin "1") (pinfunction "1_1") (pintype "passive"))
      (node (ref "E2") (pin "3") (pinfunction "O_3") (pintype "output"))
      (node (ref "R29") (pin "1") (pinfunction "1_1") (pintype "passive"))
    )
    (net (code "33") (name "Net-(E2B-I0)") (class "Default")
      (node (ref "E2") (pin "4") (pinfunction "I0_4") (pintype "input"))
      (node (ref "E2") (pin "5") (pinfunction "I1_5") (pintype "input"))
      (node (ref "E4") (pin "13") (pinfunction "O_13") (pintype "output"))
    )
    (net (code "34") (name "Net-(E2B-O)") (class "Default")
      (node (ref "C15") (pin "1") (pinfunction "1_1") (pintype "passive"))
      (node (ref "E2") (pin "6") (pinfunction "O_6") (pintype "output"))
      (node (ref "R31") (pin "1") (pinfunction "1_1") (pintype "passive"))
    )
    (net (code "35") (name "Net-(E2C-I0)") (class "Default")
      (node (ref "E2") (pin "9") (pinfunction "I0_9") (pintype "input"))
      (node (ref "E8") (pin "3") (pinfunction "O_3") (pintype "output"))
      (node (ref "E9") (pin "4") (pinfunction "I0_4") (pintype "input"))
    )
    (net (code "36") (name "Net-(E2C-O)") (class "Default")
      (node (ref "C17") (pin "1") (pinfunction "1_1") (pintype "passive"))
      (node (ref "E2") (pin "8") (pinfunction "O_8") (pintype "output"))
      (node (ref "R35") (pin "1") (pinfunction "1_1") (pintype "passive"))
    )
    (net (code "37") (name "Net-(E2D-I1)") (class "Default")
      (node (ref "E2") (pin "13") (pinfunction "I1_13") (pintype "input"))
      (node (ref "E6") (pin "14") (pinfunction "O_14") (pintype "output"))
      (node (ref "E9") (pin "1") (pinfunction "I0_1") (pintype "input"))
    )
    (net (code "38") (name "Net-(E2D-O)") (class "Default")
      (node (ref "C16") (pin "1") (pinfunction "1_1") (pintype "passive"))
      (node (ref "E2") (pin "11") (pinfunction "O_11") (pintype "output"))
      (node (ref "R33") (pin "1") (pinfunction "1_1") (pintype "passive"))
    )
    (net (code "39") (name "Net-(E3A-I)") (class "Default")
      (node (ref "E3") (pin "1") (pinfunction "I_1") (pintype "input"))
      (node (ref "EDGE") (pin "BD2") (pinfunction "1_BD2") (pintype "bidirectional"))
    )
    (net (code "40") (name "Net-(E3B-I)") (class "Default")
      (node (ref "E3") (pin "3") (pinfunction "I_3") (pintype "input"))
      (node (ref "E6") (pin "6") (pinfunction "I0_6") (pintype "input"))
      (node (ref "EDGE") (pin "BE2") (pinfunction "1_BE2") (pintype "bidirectional"))
    )
    (net (code "41") (name "Net-(E3B-O)") (class "Default")
      (node (ref "E3") (pin "4") (pinfunction "O_4") (pintype "output"))
      (node (ref "E8") (pin "11") (pinfunction "I0_11") (pintype "input"))
    )
    (net (code "42") (name "Net-(E3C-I)") (class "Default")
      (node (ref "E3") (pin "5") (pinfunction "I_5") (pintype "input"))
      (node (ref "EDGE") (pin "BD1") (pinfunction "1_BD1") (pintype "bidirectional"))
    )
    (net (code "43") (name "Net-(E3C-O)") (class "Default")
      (node (ref "E3") (pin "6") (pinfunction "O_6") (pintype "output"))
      (node (ref "E7") (pin "5") (pinfunction "I_5") (pintype "input"))
      (node (ref "EDGE") (pin "BC1") (pinfunction "1_BC1") (pintype "bidirectional"))
    )
    (net (code "44") (name "Net-(E3D-I)") (class "Default")
      (node (ref "D28") (pin "A") (pinfunction "A_A") (pintype "passive"))
      (node (ref "E3") (pin "9") (pinfunction "I_9") (pintype "input"))
      (node (ref "EDGE") (pin "AT2") (pinfunction "1_AT2") (pintype "bidirectional"))
      (node (ref "Q8") (pin "3") (pinfunction "C_3") (pintype "passive"))
      (node (ref "R17") (pin "1") (pinfunction "1_1") (pintype "passive"))
    )
    (net (code "45") (name "Net-(E3D-O)") (class "Default")
      (node (ref "E3") (pin "8") (pinfunction "O_8") (pintype "output"))
      (node (ref "EDGE") (pin "BB1") (pinfunction "1_BB1") (pintype "bidirectional"))
    )
    (net (code "46") (name "Net-(E3E-I)") (class "Default")
      (node (ref "D32") (pin "A") (pinfunction "A_A") (pintype "passive"))
      (node (ref "E3") (pin "11") (pinfunction "I_11") (pintype "input"))
      (node (ref "EDGE") (pin "AS2") (pinfunction "1_AS2") (pintype "bidirectional"))
      (node (ref "Q10") (pin "3") (pinfunction "C_3") (pintype "passive"))
      (node (ref "R19") (pin "1") (pinfunction "1_1") (pintype "passive"))
    )
    (net (code "47") (name "Net-(E3E-O)") (class "Default")
      (node (ref "E3") (pin "10") (pinfunction "O_10") (pintype "output"))
      (node (ref "EDGE") (pin "BA1") (pinfunction "1_BA1") (pintype "bidirectional"))
    )
    (net (code "48") (name "Net-(E3F-I)") (class "Default")
      (node (ref "E3") (pin "13") (pinfunction "I_13") (pintype "input"))
      (node (ref "EDGE") (pin "AV1") (pinfunction "1_AV1") (pintype "bidirectional"))
    )
    (net (code "49") (name "Net-(E3F-O)") (class "Default")
      (node (ref "E3") (pin "12") (pinfunction "O_12") (pintype "output"))
      (node (ref "EDGE") (pin "AU1") (pinfunction "1_AU1") (pintype "bidirectional"))
    )
    (net (code "50") (name "Net-(E4A-I0)") (class "Default")
      (node (ref "E4") (pin "4") (pinfunction "I0_4") (pintype "input"))
      (node (ref "E4") (pin "5") (pinfunction "I1_5") (pintype "input"))
      (node (ref "EDGE") (pin "BS2") (pinfunction "1_BS2") (pintype "bidirectional"))
    )
    (net (code "51") (name "Net-(E4B-I0)") (class "Default")
      (node (ref "E4") (pin "6") (pinfunction "I0_6") (pintype "input"))
      (node (ref "E4") (pin "7") (pinfunction "I1_7") (pintype "input"))
      (node (ref "EDGE") (pin "BR2") (pinfunction "1_BR2") (pintype "bidirectional"))
    )
    (net (code "52") (name "Net-(E4B-O)") (class "Default")
      (node (ref "E4") (pin "2") (pinfunction "O_2") (pintype "output"))
      (node (ref "E5") (pin "4") (pinfunction "I0_4") (pintype "input"))
      (node (ref "E5") (pin "5") (pinfunction "I1_5") (pintype "input"))
    )
    (net (code "53") (name "Net-(E4C-I0)") (class "Default")
      (node (ref "E4") (pin "10") (pinfunction "I1_10") (pintype "input"))
      (node (ref "E4") (pin "9") (pinfunction "I0_9") (pintype "input"))
      (node (ref "EDGE") (pin "BN2") (pinfunction "1_BN2") (pintype "bidirectional"))
    )
    (net (code "54") (name "Net-(E4C-O)") (class "Default")
      (node (ref "E4") (pin "14") (pinfunction "O_14") (pintype "output"))
      (node (ref "E5") (pin "10") (pinfunction "I1_10") (pintype "input"))
      (node (ref "E5") (pin "9") (pinfunction "I0_9") (pintype "input"))
    )
    (net (code "55") (name "Net-(E4D-I0)") (class "Default")
      (node (ref "E4") (pin "11") (pinfunction "I0_11") (pintype "input"))
      (node (ref "E4") (pin "12") (pinfunction "I1_12") (pintype "input"))
      (node (ref "EDGE") (pin "BP2") (pinfunction "1_BP2") (pintype "bidirectional"))
    )
    (net (code "56") (name "Net-(E5A-I0)") (class "Default")
      (node (ref "E5") (pin "1") (pinfunction "I0_1") (pintype "input"))
      (node (ref "E5") (pin "2") (pinfunction "I1_2") (pintype "input"))
      (node (ref "EDGE") (pin "BV1") (pinfunction "1_BV1") (pintype "bidirectional"))
    )
    (net (code "57") (name "Net-(E5A-O)") (class "Default")
      (node (ref "C10") (pin "1") (pinfunction "1_1") (pintype "passive"))
      (node (ref "E5") (pin "3") (pinfunction "O_3") (pintype "output"))
      (node (ref "R21") (pin "1") (pinfunction "1_1") (pintype "passive"))
    )
    (net (code "58") (name "Net-(E5B-O)") (class "Default")
      (node (ref "C11") (pin "1") (pinfunction "1_1") (pintype "passive"))
      (node (ref "E5") (pin "6") (pinfunction "O_6") (pintype "output"))
      (node (ref "R23") (pin "1") (pinfunction "1_1") (pintype "passive"))
    )
    (net (code "59") (name "Net-(E5C-O)") (class "Default")
      (node (ref "C13") (pin "1") (pinfunction "1_1") (pintype "passive"))
      (node (ref "E5") (pin "8") (pinfunction "O_8") (pintype "output"))
      (node (ref "R27") (pin "1") (pinfunction "1_1") (pintype "passive"))
    )
    (net (code "60") (name "Net-(E5D-I0)") (class "Default")
      (node (ref "E5") (pin "12") (pinfunction "I0_12") (pintype "input"))
      (node (ref "E5") (pin "13") (pinfunction "I1_13") (pintype "input"))
      (node (ref "E8") (pin "2") (pinfunction "O_2") (pintype "output"))
      (node (ref "EDGE") (pin "BU2") (pinfunction "1_BU2") (pintype "bidirectional"))
    )
    (net (code "61") (name "Net-(E5D-O)") (class "Default")
      (node (ref "C12") (pin "1") (pinfunction "1_1") (pintype "passive"))
      (node (ref "E5") (pin "11") (pinfunction "O_11") (pintype "output"))
      (node (ref "R25") (pin "1") (pinfunction "1_1") (pintype "passive"))
    )
    (net (code "62") (name "Net-(E6A-I0)") (class "Default")
      (node (ref "E6") (pin "4") (pinfunction "I0_4") (pintype "input"))
      (node (ref "EDGE") (pin "BK1") (pinfunction "1_BK1") (pintype "bidirectional"))
    )
    (net (code "63") (name "Net-(E6A-I1)") (class "Default")
      (node (ref "E6") (pin "5") (pinfunction "I1_5") (pintype "input"))
      (node (ref "EDGE") (pin "BL1") (pinfunction "1_BL1") (pintype "bidirectional"))
    )
    (net (code "64") (name "Net-(E6A-O)") (class "Default")
      (node (ref "E6") (pin "3") (pinfunction "O_3") (pintype "output"))
      (node (ref "EDGE") (pin "BM1") (pinfunction "1_BM1") (pintype "bidirectional"))
    )
    (net (code "65") (name "Net-(E6D-I0)") (class "Default")
      (node (ref "E6") (pin "11") (pinfunction "I0_11") (pintype "input"))
      (node (ref "EDGE") (pin "BJ1") (pinfunction "1_BJ1") (pintype "bidirectional"))
    )
    (net (code "66") (name "Net-(E6D-I1)") (class "Default")
      (node (ref "E6") (pin "12") (pinfunction "I1_12") (pintype "input"))
      (node (ref "EDGE") (pin "BH1") (pinfunction "1_BH1") (pintype "bidirectional"))
    )
    (net (code "67") (name "Net-(E6D-O)") (class "Default")
      (node (ref "E6") (pin "13") (pinfunction "O_13") (pintype "output"))
      (node (ref "EDGE") (pin "BF1") (pinfunction "1_BF1") (pintype "bidirectional"))
    )
    (net (code "68") (name "Net-(E7C-O)") (class "Default")
      (node (ref "E7") (pin "6") (pinfunction "O_6") (pintype "open_collector"))
      (node (ref "EDGE") (pin "BV2") (pinfunction "1_BV2") (pintype "bidirectional"))
    )
    (net (code "69") (name "Net-(E7D-I)") (class "Default")
      (node (ref "E7") (pin "9") (pinfunction "I_9") (pintype "input"))
      (node (ref "Q6") (pin "3") (pinfunction "C_3") (pintype "passive"))
      (node (ref "R15") (pin "1") (pinfunction "1_1") (pintype "passive"))
    )
    (net (code "70") (name "Net-(E7D-O)") (class "Default")
      (node (ref "E7") (pin "8") (pinfunction "O_8") (pintype "open_collector"))
      (node (ref "EDGE") (pin "BF2") (pinfunction "1_BF2") (pintype "bidirectional"))
    )
    (net (code "71") (name "Net-(E7E-I)") (class "Default")
      (node (ref "E7") (pin "11") (pinfunction "I_11") (pintype "input"))
      (node (ref "Q7") (pin "3") (pinfunction "C_3") (pintype "passive"))
      (node (ref "R18") (pin "1") (pinfunction "1_1") (pintype "passive"))
    )
    (net (code "72") (name "Net-(E7E-O)") (class "Default")
      (node (ref "E7") (pin "10") (pinfunction "O_10") (pintype "open_collector"))
      (node (ref "EDGE") (pin "BH2") (pinfunction "1_BH2") (pintype "bidirectional"))
    )
    (net (code "73") (name "Net-(E7F-I)") (class "Default")
      (node (ref "E7") (pin "13") (pinfunction "I_13") (pintype "input"))
      (node (ref "Q9") (pin "3") (pinfunction "C_3") (pintype "passive"))
      (node (ref "R20") (pin "1") (pinfunction "1_1") (pintype "passive"))
    )
    (net (code "74") (name "Net-(E7F-O)") (class "Default")
      (node (ref "E7") (pin "12") (pinfunction "O_12") (pintype "open_collector"))
      (node (ref "EDGE") (pin "BJ2") (pinfunction "1_BJ2") (pintype "bidirectional"))
    )
    (net (code "75") (name "Net-(E8B-I0)") (class "Default")
      (node (ref "E8") (pin "6") (pinfunction "I0_6") (pintype "input"))
      (node (ref "E8") (pin "7") (pinfunction "I1_7") (pintype "input"))
      (node (ref "EDGE") (pin "BU1") (pinfunction "1_BU1") (pintype "bidirectional"))
    )
    (net (code "76") (name "Net-(E8C-O)") (class "Default")
      (node (ref "E8") (pin "14") (pinfunction "O_14") (pintype "output"))
      (node (ref "E9") (pin "12") (pinfunction "I0_12") (pintype "input"))
      (node (ref "E9") (pin "9") (pinfunction "I0_9") (pintype "input"))
    )
    (net (code "77") (name "Net-(E9A-O)") (class "Default")
      (node (ref "C19") (pin "1") (pinfunction "1_1") (pintype "passive"))
      (node (ref "E9") (pin "3") (pinfunction "O_3") (pintype "output"))
      (node (ref "R39") (pin "1") (pinfunction "1_1") (pintype "passive"))
    )
    (net (code "78") (name "Net-(E9B-O)") (class "Default")
      (node (ref "C18") (pin "1") (pinfunction "1_1") (pintype "passive"))
      (node (ref "E9") (pin "6") (pinfunction "O_6") (pintype "output"))
      (node (ref "R37") (pin "1") (pinfunction "1_1") (pintype "passive"))
    )
    (net (code "79") (name "Net-(E9C-O)") (class "Default")
      (node (ref "C20") (pin "1") (pinfunction "1_1") (pintype "passive"))
      (node (ref "E9") (pin "8") (pinfunction "O_8") (pintype "output"))
      (node (ref "R41") (pin "1") (pinfunction "1_1") (pintype "passive"))
    )
    (net (code "80") (name "Net-(E9D-O)") (class "Default")
      (node (ref "C21") (pin "1") (pinfunction "1_1") (pintype "passive"))
      (node (ref "E9") (pin "11") (pinfunction "O_11") (pintype "output"))
      (node (ref "R43") (pin "1") (pinfunction "1_1") (pintype "passive"))
    )
    (net (code "81") (name "Net-(E10A-I)") (class "Default")
      (node (ref "D40") (pin "A") (pinfunction "A_A") (pintype "passive"))
      (node (ref "E10") (pin "1") (pinfunction "I_1") (pintype "input"))
      (node (ref "Q3") (pin "3") (pinfunction "C_3") (pintype "passive"))
      (node (ref "R14") (pin "1") (pinfunction "1_1") (pintype "passive"))
    )
    (net (code "82") (name "Net-(E10A-O)") (class "Default")
      (node (ref "E10") (pin "2") (pinfunction "O_2") (pintype "output"))
      (node (ref "EDGE") (pin "AM2") (pinfunction "1_AM2") (pintype "bidirectional"))
    )
    (net (code "83") (name "Net-(E10B-I)") (class "Default")
      (node (ref "D36") (pin "A") (pinfunction "A_A") (pintype "passive"))
      (node (ref "E10") (pin "3") (pinfunction "I_3") (pintype "input"))
      (node (ref "Q2") (pin "3") (pinfunction "C_3") (pintype "passive"))
      (node (ref "R11") (pin "1") (pinfunction "1_1") (pintype "passive"))
    )
    (net (code "84") (name "Net-(E10B-O)") (class "Default")
      (node (ref "E10") (pin "4") (pinfunction "O_4") (pintype "output"))
      (node (ref "EDGE") (pin "AN2") (pinfunction "1_AN2") (pintype "bidirectional"))
    )
    (net (code "85") (name "Net-(EDGEA-1)") (class "Default")
      (node (ref "D47") (pin "C") (pinfunction "C_C") (pintype "passive"))
      (node (ref "EDGE") (pin "AA1") (pinfunction "1_AA1") (pintype "bidirectional"))
      (node (ref "Q12") (pin "3") (pinfunction "C_3") (pintype "passive"))
    )
    (net (code "86") (name "Net-(EDGEAA-1)") (class "Default")
      (node (ref "D17") (pin "C") (pinfunction "C_C") (pintype "passive"))
      (node (ref "D18") (pin "A") (pinfunction "A_A") (pintype "passive"))
      (node (ref "EDGE") (pin "AR1") (pinfunction "1_AR1") (pintype "bidirectional"))
      (node (ref "R9") (pin "1") (pinfunction "1_1") (pintype "passive"))
    )
    (net (code "87") (name "Net-(EDGEAB-1)") (class "Default")
      (node (ref "D19") (pin "C") (pinfunction "C_C") (pintype "passive"))
      (node (ref "D20") (pin "A") (pinfunction "A_A") (pintype "passive"))
      (node (ref "D29") (pin "C") (pinfunction "C_C") (pintype "passive"))
      (node (ref "EDGE") (pin "AR2") (pinfunction "1_AR2") (pintype "bidirectional"))
    )
    (net (code "88") (name "Net-(EDGEC-1)") (class "Default")
      (node (ref "D45") (pin "C") (pinfunction "C_C") (pintype "passive"))
      (node (ref "EDGE") (pin "AB1") (pinfunction "1_AB1") (pintype "bidirectional"))
      (node (ref "Q11") (pin "3") (pinfunction "C_3") (pintype "passive"))
    )
    (net (code "89") (name "Net-(EDGEG-1)") (class "Default")
      (node (ref "D50") (pin "C") (pinfunction "C_C") (pintype "passive"))
      (node (ref "EDGE") (pin "AD1") (pinfunction "1_AD1") (pintype "bidirectional"))
      (node (ref "Q15") (pin "3") (pinfunction "C_3") (pintype "passive"))
    )
    (net (code "90") (name "Net-(EDGEH-1)") (class "Default")
      (node (ref "D46") (pin "C") (pinfunction "C_C") (pintype "passive"))
      (node (ref "EDGE") (pin "AD2") (pinfunction "1_AD2") (pintype "bidirectional"))
      (node (ref "Q13") (pin "3") (pinfunction "C_3") (pintype "passive"))
    )
    (net (code "91") (name "Net-(EDGEI-1)") (class "Default")
      (node (ref "D48") (pin "C") (pinfunction "C_C") (pintype "passive"))
      (node (ref "EDGE") (pin "AE1") (pinfunction "1_AE1") (pintype "bidirectional"))
      (node (ref "Q14") (pin "3") (pinfunction "C_3") (pintype "passive"))
    )
    (net (code "92") (name "Net-(EDGEJ-1)") (class "Default")
      (node (ref "D49") (pin "C") (pinfunction "C_C") (pintype "passive"))
      (node (ref "EDGE") (pin "AE2") (pinfunction "1_AE2") (pintype "bidirectional"))
      (node (ref "Q16") (pin "3") (pinfunction "C_3") (pintype "passive"))
    )
    (net (code "93") (name "Net-(EDGEK-1)") (class "Default")
      (node (ref "EDGE") (pin "AF1") (pinfunction "1_AF1") (pintype "bidirectional"))
      (node (ref "Q17") (pin "3") (pinfunction "C_3") (pintype "passive"))
    )
    (net (code "94") (name "Net-(EDGEL-1)") (class "Default")
      (node (ref "D52") (pin "C") (pinfunction "C_C") (pintype "passive"))
      (node (ref "EDGE") (pin "AF2") (pinfunction "1_AF2") (pintype "bidirectional"))
      (node (ref "Q19") (pin "3") (pinfunction "C_3") (pintype "passive"))
    )
    (net (code "95") (name "Net-(EDGEM-1)") (class "Default")
      (node (ref "EDGE") (pin "AH1") (pinfunction "1_AH1") (pintype "bidirectional"))
      (node (ref "Q20") (pin "3") (pinfunction "C_3") (pintype "passive"))
    )
    (net (code "96") (name "Net-(EDGEN-1)") (class "Default")
      (node (ref "D51") (pin "C") (pinfunction "C_C") (pintype "passive"))
      (node (ref "EDGE") (pin "AH2") (pinfunction "1_AH2") (pintype "bidirectional"))
      (node (ref "Q22") (pin "3") (pinfunction "C_3") (pintype "passive"))
    )
    (net (code "97") (name "Net-(EDGEO-1)") (class "Default")
      (node (ref "EDGE") (pin "AJ1") (pinfunction "1_AJ1") (pintype "bidirectional"))
      (node (ref "Q21") (pin "3") (pinfunction "C_3") (pintype "passive"))
    )
    (net (code "98") (name "Net-(EDGEP-1)") (class "Default")
      (node (ref "D53") (pin "C") (pinfunction "C_C") (pintype "passive"))
      (node (ref "EDGE") (pin "AJ2") (pinfunction "1_AJ2") (pintype "bidirectional"))
      (node (ref "Q18") (pin "3") (pinfunction "C_3") (pintype "passive"))
    )
    (net (code "99") (name "Net-(EDGEQ-1)") (class "Default")
      (node (ref "D1") (pin "C") (pinfunction "C_C") (pintype "passive"))
      (node (ref "D2") (pin "A") (pinfunction "A_A") (pintype "passive"))
      (node (ref "EDGE") (pin "AK1") (pinfunction "1_AK1") (pintype "bidirectional"))
      (node (ref "R1") (pin "1") (pinfunction "1_1") (pintype "passive"))
    )
    (net (code "100") (name "Net-(EDGER-1)") (class "Default")
      (node (ref "D3") (pin "C") (pinfunction "C_C") (pintype "passive"))
      (node (ref "D33") (pin "C") (pinfunction "C_C") (pintype "passive"))
      (node (ref "D4") (pin "A") (pinfunction "A_A") (pintype "passive"))
      (node (ref "EDGE") (pin "AK2") (pinfunction "1_AK2") (pintype "bidirectional"))
    )
    (net (code "101") (name "Net-(EDGES-1)") (class "Default")
      (node (ref "D7") (pin "C") (pinfunction "C_C") (pintype "passive"))
      (node (ref "D8") (pin "A") (pinfunction "A_A") (pintype "passive"))
      (node (ref "EDGE") (pin "AL1") (pinfunction "1_AL1") (pintype "bidirectional"))
      (node (ref "R4") (pin "1") (pinfunction "1_1") (pintype "passive"))
    )
    (net (code "102") (name "Net-(EDGET-1)") (class "Default")
      (node (ref "D37") (pin "C") (pinfunction "C_C") (pintype "passive"))
      (node (ref "D5") (pin "C") (pinfunction "C_C") (pintype "passive"))
      (node (ref "D6") (pin "A") (pinfunction "A_A") (pintype "passive"))
      (node (ref "EDGE") (pin "AL2") (pinfunction "1_AL2") (pintype "bidirectional"))
    )
    (net (code "103") (name "Net-(EDGEU-1)") (class "Default")
      (node (ref "D10") (pin "A") (pinfunction "A_A") (pintype "passive"))
      (node (ref "D9") (pin "C") (pinfunction "C_C") (pintype "passive"))
      (node (ref "EDGE") (pin "AM1") (pinfunction "1_AM1") (pintype "bidirectional"))
      (node (ref "R5") (pin "1") (pinfunction "1_1") (pintype "passive"))
    )
    (net (code "104") (name "Net-(EDGEW-1)") (class "Default")
      (node (ref "D11") (pin "C") (pinfunction "C_C") (pintype "passive"))
      (node (ref "D12") (pin "A") (pinfunction "A_A") (pintype "passive"))
      (node (ref "EDGE") (pin "AN1") (pinfunction "1_AN1") (pintype "bidirectional"))
      (node (ref "R6") (pin "1") (pinfunction "1_1") (pintype "passive"))
    )
    (net (code "105") (name "Net-(EDGEY-1)") (class "Default")
      (node (ref "D13") (pin "C") (pinfunction "C_C") (pintype "passive"))
      (node (ref "D14") (pin "A") (pinfunction "A_A") (pintype "passive"))
      (node (ref "EDGE") (pin "AP1") (pinfunction "1_AP1") (pintype "bidirectional"))
      (node (ref "R7") (pin "1") (pinfunction "1_1") (pintype "passive"))
    )
    (net (code "106") (name "Net-(EDGEZ-1)") (class "Default")
      (node (ref "D15") (pin "C") (pinfunction "C_C") (pintype "passive"))
      (node (ref "D16") (pin "A") (pinfunction "A_A") (pintype "passive"))
      (node (ref "D25") (pin "C") (pinfunction "C_C") (pintype "passive"))
      (node (ref "EDGE") (pin "AP2") (pinfunction "1_AP2") (pintype "bidirectional"))
    )
    (net (code "107") (name "Net-(Q1-E)") (class "Default")
      (node (ref "Q1") (pin "1") (pinfunction "E_1") (pintype "passive"))
      (node (ref "R1") (pin "2") (pinfunction "2_2") (pintype "passive"))
    )
    (net (code "108") (name "Net-(Q2-B)") (class "Default")
      (node (ref "D35") (pin "A") (pinfunction "A_A") (pintype "passive"))
      (node (ref "Q2") (pin "2") (pinfunction "B_2") (pintype "passive"))
      (node (ref "R48") (pin "1") (pinfunction "1_1") (pintype "passive"))
    )
    (net (code "109") (name "Net-(Q3-B)") (class "Default")
      (node (ref "D39") (pin "A") (pinfunction "A_A") (pintype "passive"))
      (node (ref "Q3") (pin "2") (pinfunction "B_2") (pintype "passive"))
      (node (ref "R49") (pin "1") (pinfunction "1_1") (pintype "passive"))
    )
    (net (code "110") (name "Net-(Q4-E)") (class "Default")
      (node (ref "Q4") (pin "1") (pinfunction "E_1") (pintype "passive"))
      (node (ref "R4") (pin "2") (pinfunction "2_2") (pintype "passive"))
    )
    (net (code "111") (name "Net-(Q5-E)") (class "Default")
      (node (ref "Q5") (pin "1") (pinfunction "E_1") (pintype "passive"))
      (node (ref "R5") (pin "2") (pinfunction "2_2") (pintype "passive"))
    )
    (net (code "112") (name "Net-(Q6-E)") (class "Default")
      (node (ref "Q6") (pin "1") (pinfunction "E_1") (pintype "passive"))
      (node (ref "R6") (pin "2") (pinfunction "2_2") (pintype "passive"))
    )
    (net (code "113") (name "Net-(Q7-E)") (class "Default")
      (node (ref "Q7") (pin "1") (pinfunction "E_1") (pintype "passive"))
      (node (ref "R7") (pin "2") (pinfunction "2_2") (pintype "passive"))
    )
    (net (code "114") (name "Net-(Q8-B)") (class "Default")
      (node (ref "D27") (pin "A") (pinfunction "A_A") (pintype "passive"))
      (node (ref "Q8") (pin "2") (pinfunction "B_2") (pintype "passive"))
      (node (ref "R46") (pin "1") (pinfunction "1_1") (pintype "passive"))
    )
    (net (code "115") (name "Net-(Q9-E)") (class "Default")
      (node (ref "Q9") (pin "1") (pinfunction "E_1") (pintype "passive"))
      (node (ref "R9") (pin "2") (pinfunction "2_2") (pintype "passive"))
    )
    (net (code "116") (name "Net-(Q10-B)") (class "Default")
      (node (ref "D31") (pin "A") (pinfunction "A_A") (pintype "passive"))
      (node (ref "Q10") (pin "2") (pinfunction "B_2") (pintype "passive"))
      (node (ref "R47") (pin "1") (pinfunction "1_1") (pintype "passive"))
    )
    (net (code "117") (name "Net-(Q11-B)") (class "Default")
      (node (ref "C12") (pin "2") (pinfunction "2_2") (pintype "passive"))
      (node (ref "Q11") (pin "2") (pinfunction "B_2") (pintype "passive"))
      (node (ref "R25") (pin "2") (pinfunction "2_2") (pintype "passive"))
      (node (ref "R26") (pin "1") (pinfunction "1_1") (pintype "passive"))
    )
    (net (code "118") (name "Net-(Q12-B)") (class "Default")
      (node (ref "C10") (pin "2") (pinfunction "2_2") (pintype "passive"))
      (node (ref "Q12") (pin "2") (pinfunction "B_2") (pintype "passive"))
      (node (ref "R21") (pin "2") (pinfunction "2_2") (pintype "passive"))
      (node (ref "R22") (pin "1") (pinfunction "1_1") (pintype "passive"))
    )
    (net (code "119") (name "Net-(Q13-B)") (class "Default")
      (node (ref "C11") (pin "2") (pinfunction "2_2") (pintype "passive"))
      (node (ref "Q13") (pin "2") (pinfunction "B_2") (pintype "passive"))
      (node (ref "R23") (pin "2") (pinfunction "2_2") (pintype "passive"))
      (node (ref "R24") (pin "1") (pinfunction "1_1") (pintype "passive"))
    )
    (net (code "120") (name "Net-(Q14-B)") (class "Default")
      (node (ref "C15") (pin "2") (pinfunction "2_2") (pintype "passive"))
      (node (ref "Q14") (pin "2") (pinfunction "B_2") (pintype "passive"))
      (node (ref "R31") (pin "2") (pinfunction "2_2") (pintype "passive"))
      (node (ref "R32") (pin "1") (pinfunction "1_1") (pintype "passive"))
    )
    (net (code "121") (name "Net-(Q15-B)") (class "Default")
      (node (ref "C13") (pin "2") (pinfunction "2_2") (pintype "passive"))
      (node (ref "Q15") (pin "2") (pinfunction "B_2") (pintype "passive"))
      (node (ref "R27") (pin "2") (pinfunction "2_2") (pintype "passive"))
      (node (ref "R28") (pin "1") (pinfunction "1_1") (pintype "passive"))
    )
    (net (code "122") (name "Net-(Q16-B)") (class "Default")
      (node (ref "C14") (pin "2") (pinfunction "2_2") (pintype "passive"))
      (node (ref "Q16") (pin "2") (pinfunction "B_2") (pintype "passive"))
      (node (ref "R29") (pin "2") (pinfunction "2_2") (pintype "passive"))
      (node (ref "R30") (pin "1") (pinfunction "1_1") (pintype "passive"))
    )
    (net (code "123") (name "Net-(Q17-B)") (class "Default")
      (node (ref "C18") (pin "2") (pinfunction "2_2") (pintype "passive"))
      (node (ref "Q17") (pin "2") (pinfunction "B_2") (pintype "passive"))
      (node (ref "R37") (pin "2") (pinfunction "2_2") (pintype "passive"))
      (node (ref "R38") (pin "1") (pinfunction "1_1") (pintype "passive"))
    )
    (net (code "124") (name "Net-(Q18-B)") (class "Default")
      (node (ref "C16") (pin "2") (pinfunction "2_2") (pintype "passive"))
      (node (ref "Q18") (pin "2") (pinfunction "B_2") (pintype "passive"))
      (node (ref "R33") (pin "2") (pinfunction "2_2") (pintype "passive"))
      (node (ref "R34") (pin "1") (pinfunction "1_1") (pintype "passive"))
    )
    (net (code "125") (name "Net-(Q19-B)") (class "Default")
      (node (ref "C17") (pin "2") (pinfunction "2_2") (pintype "passive"))
      (node (ref "Q19") (pin "2") (pinfunction "B_2") (pintype "passive"))
      (node (ref "R35") (pin "2") (pinfunction "2_2") (pintype "passive"))
      (node (ref "R36") (pin "1") (pinfunction "1_1") (pintype "passive"))
    )
    (net (code "126") (name "Net-(Q20-B)") (class "Default")
      (node (ref "C21") (pin "2") (pinfunction "2_2") (pintype "passive"))
      (node (ref "Q20") (pin "2") (pinfunction "B_2") (pintype "passive"))
      (node (ref "R43") (pin "2") (pinfunction "2_2") (pintype "passive"))
      (node (ref "R44") (pin "1") (pinfunction "1_1") (pintype "passive"))
    )
    (net (code "127") (name "Net-(Q21-B)") (class "Default")
      (node (ref "C19") (pin "2") (pinfunction "2_2") (pintype "passive"))
      (node (ref "Q21") (pin "2") (pinfunction "B_2") (pintype "passive"))
      (node (ref "R39") (pin "2") (pinfunction "2_2") (pintype "passive"))
      (node (ref "R40") (pin "1") (pinfunction "1_1") (pintype "passive"))
    )
    (net (code "128") (name "Net-(Q22-B)") (class "Default")
      (node (ref "C20") (pin "2") (pinfunction "2_2") (pintype "passive"))
      (node (ref "Q22") (pin "2") (pinfunction "B_2") (pintype "passive"))
      (node (ref "R41") (pin "2") (pinfunction "2_2") (pintype "passive"))
      (node (ref "R42") (pin "1") (pinfunction "1_1") (pintype "passive"))
    )
    (net (code "129") (name "VCC") (class "Default")
      (node (ref "C1") (pin "1") (pinfunction "1_1") (pintype "passive"))
      (node (ref "C2") (pin "1") (pinfunction "1_1") (pintype "passive"))
      (node (ref "C23") (pin "+") (pinfunction "+_+") (pintype "passive"))
      (node (ref "C25") (pin "+") (pinfunction "+_+") (pintype "passive"))
      (node (ref "C29") (pin "1") (pinfunction "1_1") (pintype "passive"))
      (node (ref "C3") (pin "1") (pinfunction "1_1") (pintype "passive"))
      (node (ref "C4") (pin "1") (pinfunction "1_1") (pintype "passive"))
      (node (ref "C5") (pin "1") (pinfunction "1_1") (pintype "passive"))
      (node (ref "C6") (pin "1") (pinfunction "1_1") (pintype "passive"))
      (node (ref "C7") (pin "1") (pinfunction "1_1") (pintype "passive"))
      (node (ref "C8") (pin "1") (pinfunction "1_1") (pintype "passive"))
      (node (ref "C9") (pin "1") (pinfunction "1_1") (pintype "passive"))
      (node (ref "EDGE") (pin "AA2") (pinfunction "1_AA2") (pintype "bidirectional"))
      (node (ref "EDGE") (pin "BA2") (pinfunction "1_BA2") (pintype "bidirectional"))
      (node (ref "R11") (pin "2") (pinfunction "2_2") (pintype "passive"))
      (node (ref "R12") (pin "2") (pinfunction "2_2") (pintype "passive"))
      (node (ref "R13") (pin "2") (pinfunction "2_2") (pintype "passive"))
      (node (ref "R14") (pin "2") (pinfunction "2_2") (pintype "passive"))
      (node (ref "R15") (pin "2") (pinfunction "2_2") (pintype "passive"))
      (node (ref "R16") (pin "2") (pinfunction "2_2") (pintype "passive"))
      (node (ref "R17") (pin "2") (pinfunction "2_2") (pintype "passive"))
      (node (ref "R18") (pin "2") (pinfunction "2_2") (pintype "passive"))
      (node (ref "R19") (pin "2") (pinfunction "2_2") (pintype "passive"))
      (node (ref "R20") (pin "2") (pinfunction "2_2") (pintype "passive"))
      (node (ref "R46") (pin "2") (pinfunction "2_2") (pintype "passive"))
      (node (ref "R47") (pin "2") (pinfunction "2_2") (pintype "passive"))
      (node (ref "R48") (pin "2") (pinfunction "2_2") (pintype "passive"))
      (node (ref "R49") (pin "2") (pinfunction "2_2") (pintype "passive"))
      (node (ref "R50") (pin "2") (pinfunction "2_2") (pintype "passive"))
      (node (ref "R51") (pin "2") (pinfunction "2_2") (pintype "passive"))
    )
  )
)
